# -1V_DIST.net
KiCad netlist of a schematic drawn in Altium Designer
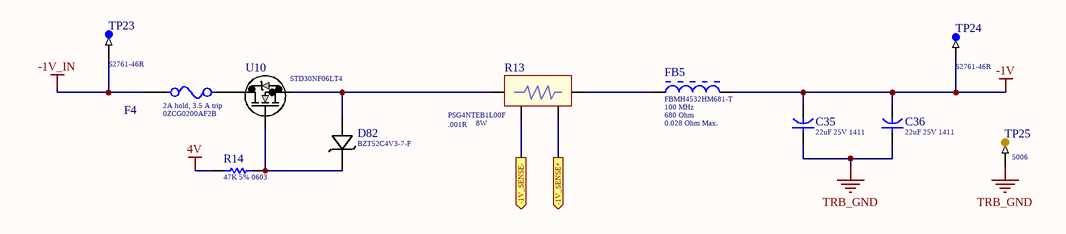
[diagram p0: -1V_DIST.SchDoc]

(export (version "E")
  (design (tool "Eeschema 10.0.6"))
  (components
    (comp (ref "C35")
      (value "Cap_Kemet_T521B226M025ATE100_22uF")
      (footprint "Cap_Kemet_T521B226M025ATE100_22uF")
      (description "Tantalum Capacitors - Polymer SMD 25V 22uF 1311 20% ESR=100mOhms")
      (fields (field (name "CAPACITANCE") "22uF 25V 1411"))
      (libsource (lib "Cap_Kemet_T521B226M025ATE100_22uF") (part "Cap_Kemet_T521B226M025ATE100_22uF"))
    )
    (comp (ref "C36")
      (value "Cap_Kemet_T521B226M025ATE100_22uF")
      (footprint "Cap_Kemet_T521B226M025ATE100_22uF")
      (description "Tantalum Capacitors - Polymer SMD 25V 22uF 1311 20% ESR=100mOhms")
      (fields (field (name "CAPACITANCE") "22uF 25V 1411"))
      (libsource (lib "Cap_Kemet_T521B226M025ATE100_22uF") (part "Cap_Kemet_T521B226M025ATE100_22uF"))
    )
    (comp (ref "D82")
      (value "BZT52C4V3-7-F")
      (footprint "SOD123")
      (description "Zener Diodes 500mW 4.3V Zener AEC-Q101 Qualified")
      (fields (field (name "SERIES") "BZT52C4V3-7-F"))
      (libsource (lib "4v3_zener_BZT52C4V3-7-F") (part "BZT52C4V3-7-F"))
    )
    (comp (ref "F4")
      (value "2A hold, 3.5 A trip")
      (footprint "Bel_0ZCG_MFG")
      (description "2A hold, 3.5A trip")
      (fields (field (name "SERIES") "0ZCG0200AF2B"))
      (libsource (lib "Fuse_Bel_0ZCG0200AF2B_rst_smd") (part "0ZCG0200AF2B"))
    )
    (comp (ref "FB5")
      (value "FBMH4532HM681-T")
      (footprint "TAYO-FBMH4532-2_V")
      (fields
        (field (name "PARTNUMBER") "FBMH4532HM681-T")
        (field (name "MANUFACTURER") "Taiyo Yuden")
        (field (name "MEASURING FREQUENCY") "100 MHz")
        (field (name "NOMINAL IMPEDANCE") "680 Ohm")
        (field (name "DC RESISTANCE") "0.028 Ohm Max.")
      )
      (libsource (lib "Taiyo_Yuden_FBMH4532HM681") (part "FBMH4532HM681-T"))
    )
    (comp (ref "R13")
      (value "SRes_KOA_PSG4NTEB1L00F_1mOhm")
      (footprint "SRes_KOA_PSG4NTEB1L00F_1mOhm")
      (description "Current Sense Resistors - SMD 1mOhm 8W 1% 50ppm AEC-Q200 Power Shunt")
      (fields
        (field (name "RESISTANCE") ".001R")
        (field (name "SERIES") "PSG4NTEB1L00F")
        (field (name "PARAMETER 1") "8W")
      )
      (libsource (lib "SRes_KOA_PSG4NTEB1L00F_1mOhm") (part "SRes_KOA_PSG4NTEB1L00F_1mOhm"))
    )
    (comp (ref "R14")
      (value "47K 5% 0603")
      (footprint "RESC0603(1608)_L")
      (description "47K 0.1W 5% 0603 (1608 Metric)  SMD")
      (fields (field (name "TOLERANCE") "5 %") (field (name "POWER") "0.1 W"))
      (libsource (lib "Altium Content Vault") (part "RES"))
    )
    (comp (ref "TP23")
      (value "TP_Harwin_S2761_46R")
      (footprint "TP_Harwin_S2761_46R")
      (description "Circuit Board Hardware - PCB SMT Mini Test Terminal, Reel")
      (fields (field (name "SERIES") "S2761-46R"))
      (libsource (lib "TP_Harwin_S2761_46R") (part "TP_Harwin_S2761_46R"))
    )
    (comp (ref "TP24")
      (value "TP_Harwin_S2761_46R")
      (footprint "TP_Harwin_S2761_46R")
      (description "Circuit Board Hardware - PCB SMT Mini Test Terminal, Reel")
      (fields (field (name "SERIES") "S2761-46R"))
      (libsource (lib "TP_Harwin_S2761_46R") (part "TP_Harwin_S2761_46R"))
    )
    (comp (ref "TP25")
      (value "TP_Keystone_Electronics_5006")
      (footprint "TP_Keystone_Electronics_5006")
      (description "Circuit Board Hardware - PCB TEST POINT BLK .063")
      (fields (field (name "SERIES") "5006"))
      (libsource (lib "TP_Keystone_Electronics_5006") (part "TP_Keystone_Electronics_5006"))
    )
    (comp (ref "U10")
      (value "STD30NF06LT4")
      (footprint "DPAK")
      (libsource (lib "STD30N6LF6AG") (part "STD30NF06LT4"))
    )
  )
  (nets
    (net (code "1") (name "-1V") (class "Default")
      (node (ref "C35") (pin "2") (pinfunction "2_2") (pintype "passive"))
      (node (ref "C36") (pin "2") (pinfunction "2_2") (pintype "passive"))
      (node (ref "FB5") (pin "2") (pinfunction "2_2") (pintype "passive"))
      (node (ref "TP24") (pin "1") (pinfunction "1_1") (pintype "input"))
    )
    (net (code "2") (name "-1V_IN") (class "Default")
      (node (ref "F4") (pin "1") (pinfunction "1_1") (pintype "passive"))
      (node (ref "TP23") (pin "1") (pinfunction "1_1") (pintype "input"))
    )
    (net (code "3") (name "/-1V_SENSE+") (class "Default")
      (node (ref "R13") (pin "3") (pinfunction "3_3") (pintype "passive"))
    )
    (net (code "4") (name "/-1V_SENSE-") (class "Default")
      (node (ref "R13") (pin "4") (pinfunction "4_4") (pintype "passive"))
    )
    (net (code "5") (name "4V") (class "Default")
      (node (ref "R14") (pin "1") (pinfunction "1_1") (pintype "passive"))
    )
    (net (code "6") (name "Net-(FB5-Pad1)") (class "Default")
      (node (ref "FB5") (pin "1") (pinfunction "1_1") (pintype "passive"))
      (node (ref "R13") (pin "2") (pinfunction "2_2") (pintype "passive"))
    )
    (net (code "7") (name "Net-(U10-D)") (class "Default")
      (node (ref "F4") (pin "2") (pinfunction "2_2") (pintype "passive"))
      (node (ref "U10") (pin "2") (pinfunction "D_2") (pintype "passive"))
    )
    (net (code "8") (name "Net-(U10-G)") (class "Default")
      (node (ref "D82") (pin "1") (pinfunction "1_1") (pintype "passive"))
      (node (ref "R14") (pin "2") (pinfunction "2_2") (pintype "passive"))
      (node (ref "U10") (pin "1") (pinfunction "G_1") (pintype "passive"))
    )
    (net (code "9") (name "Net-(U10-S)") (class "Default")
      (node (ref "D82") (pin "2") (pinfunction "2_2") (pintype "passive"))
      (node (ref "R13") (pin "1") (pinfunction "1_1") (pintype "passive"))
      (node (ref "U10") (pin "3") (pinfunction "S_3") (pintype "passive"))
    )
    (net (code "10") (name "TRB_GND") (class "Default")
      (node (ref "C35") (pin "1") (pinfunction "1_1") (pintype "passive"))
      (node (ref "C36") (pin "1") (pinfunction "1_1") (pintype "passive"))
      (node (ref "TP25") (pin "1") (pinfunction "1_1") (pintype "input"))
    )
  )
)
